# Circuit.net
KiCad netlist of a schematic drawn in EAGLE
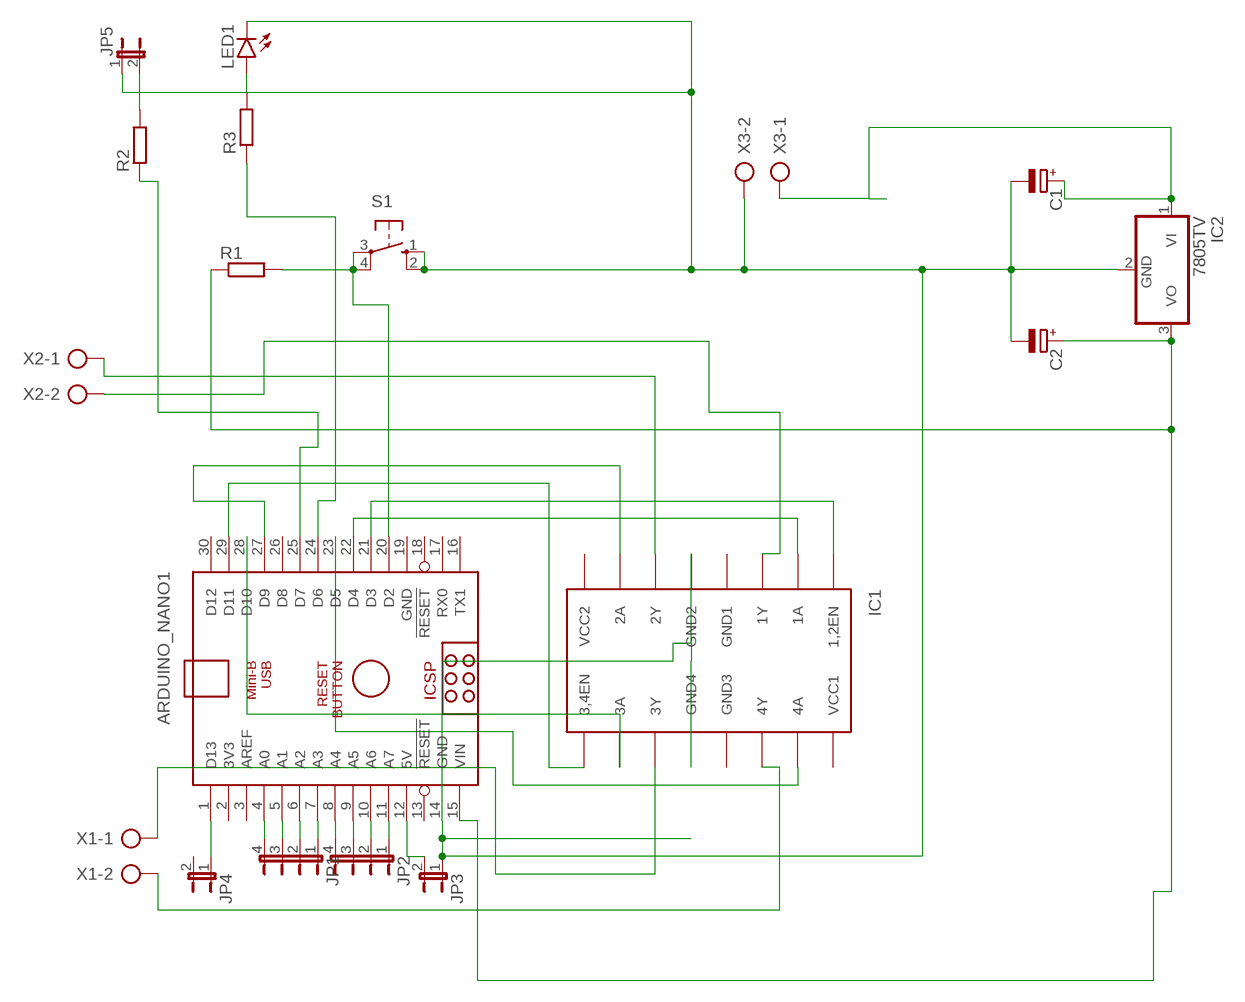
[diagram p0: schematic, sheet 1]

(export (version "E")
  (design (tool "Eeschema 10.0.6"))
  (components
    (comp (ref "ARDUINO_NANO1")
      (value "ARDUINO_NANO")
      (footprint "eagle-import:ARDUINO_NANO")
      (libsource (lib "eagle-import") (part "ARDUINO_NANO"))
    )
    (comp (ref "C1")
      (value "CPOL-EUE2.5-6")
      (footprint "eagle-import:E2,5-6")
      (libsource (lib "eagle-import") (part "CPOL-EUE2.5-6"))
    )
    (comp (ref "C2")
      (value "CPOL-EUE2.5-6")
      (footprint "eagle-import:E2,5-6")
      (libsource (lib "eagle-import") (part "CPOL-EUE2.5-6"))
    )
    (comp (ref "IC1")
      (value "L293D")
      (footprint "eagle-import:DIL16")
      (libsource (lib "eagle-import") (part "L293D"))
    )
    (comp (ref "IC2")
      (value "7805TV")
      (footprint "eagle-import:TO220V")
      (libsource (lib "eagle-import") (part "78TV05"))
    )
    (comp (ref "JP1")
      (value "JP4E")
      (footprint "eagle-import:JP4")
      (libsource (lib "eagle-import") (part "JP4E"))
    )
    (comp (ref "JP2")
      (value "JP4E")
      (footprint "eagle-import:JP4")
      (libsource (lib "eagle-import") (part "JP4E"))
    )
    (comp (ref "JP3")
      (value "JP1E")
      (footprint "eagle-import:JP1")
      (libsource (lib "eagle-import") (part "JP1E"))
    )
    (comp (ref "JP4")
      (value "JP1E")
      (footprint "eagle-import:JP1")
      (libsource (lib "eagle-import") (part "JP1E"))
    )
    (comp (ref "JP5")
      (value "JP1E")
      (footprint "eagle-import:JP1")
      (libsource (lib "eagle-import") (part "JP1E"))
    )
    (comp (ref "LED1")
      (value "LED5MM")
      (footprint "eagle-import:LED5MM")
      (libsource (lib "eagle-import") (part "LED5MM"))
    )
    (comp (ref "R1")
      (value "R-EU_0207/12")
      (footprint "eagle-import:0207_12")
      (libsource (lib "eagle-import") (part "R-EU_0207/12"))
    )
    (comp (ref "R2")
      (value "R-EU_0207/12")
      (footprint "eagle-import:0207_12")
      (libsource (lib "eagle-import") (part "R-EU_0207/12"))
    )
    (comp (ref "R3")
      (value "R-EU_0207/12")
      (footprint "eagle-import:0207_12")
      (libsource (lib "eagle-import") (part "R-EU_0207/12"))
    )
    (comp (ref "S1")
      (value "10-XX")
      (footprint "eagle-import:B3F-10XX")
      (fields (field (name "MPN") "B3F-1000"))
      (libsource (lib "eagle-import") (part "10-XX"))
    )
    (comp (ref "X1")
      (value "AK500/2")
      (footprint "eagle-import:AK500_2")
      (libsource (lib "eagle-import") (part "AK500/2"))
    )
    (comp (ref "X2")
      (value "AK500/2")
      (footprint "eagle-import:AK500_2")
      (libsource (lib "eagle-import") (part "AK500/2"))
    )
    (comp (ref "X3")
      (value "AK500/2")
      (footprint "eagle-import:AK500_2")
      (libsource (lib "eagle-import") (part "AK500/2"))
    )
  )
  (nets
    (net (code "1") (name "/GND") (class "Default")
      (node (ref "ARDUINO_NANO1") (pin "19") (pinfunction "GND_19") (pintype "power_in"))
    )
    (net (code "2") (name "/GND1") (class "Default")
      (node (ref "IC1") (pin "4") (pinfunction "GND1_4") (pintype "power_in"))
    )
    (net (code "3") (name "/GND3") (class "Default")
      (node (ref "IC1") (pin "13") (pinfunction "GND3_13") (pintype "power_in"))
    )
    (net (code "4") (name "/VCC1") (class "Default")
      (node (ref "IC1") (pin "16") (pinfunction "VCC1_16") (pintype "power_in"))
    )
    (net (code "5") (name "/VCC2") (class "Default")
      (node (ref "IC1") (pin "8") (pinfunction "VCC2_8") (pintype "power_in"))
    )
    (net (code "6") (name "Net-(ARDUINO_NANO1-5V)") (class "Default")
      (node (ref "ARDUINO_NANO1") (pin "12") (pinfunction "5V_12") (pintype "power_in"))
      (node (ref "JP3") (pin "2") (pinfunction "2_2") (pintype "passive"))
    )
    (net (code "7") (name "Net-(ARDUINO_NANO1-A0)") (class "Default")
      (node (ref "ARDUINO_NANO1") (pin "4") (pinfunction "A0_4") (pintype "bidirectional"))
      (node (ref "JP1") (pin "4") (pinfunction "4_4") (pintype "passive"))
    )
    (net (code "8") (name "Net-(ARDUINO_NANO1-A1)") (class "Default")
      (node (ref "ARDUINO_NANO1") (pin "5") (pinfunction "A1_5") (pintype "bidirectional"))
      (node (ref "JP1") (pin "3") (pinfunction "3_3") (pintype "passive"))
    )
    (net (code "9") (name "Net-(ARDUINO_NANO1-A2)") (class "Default")
      (node (ref "ARDUINO_NANO1") (pin "6") (pinfunction "A2_6") (pintype "bidirectional"))
      (node (ref "JP1") (pin "2") (pinfunction "2_2") (pintype "passive"))
    )
    (net (code "10") (name "Net-(ARDUINO_NANO1-A3)") (class "Default")
      (node (ref "ARDUINO_NANO1") (pin "7") (pinfunction "A3_7") (pintype "bidirectional"))
      (node (ref "JP1") (pin "1") (pinfunction "1_1") (pintype "passive"))
    )
    (net (code "11") (name "Net-(ARDUINO_NANO1-A4)") (class "Default")
      (node (ref "ARDUINO_NANO1") (pin "8") (pinfunction "A4_8") (pintype "bidirectional"))
      (node (ref "JP2") (pin "4") (pinfunction "4_4") (pintype "passive"))
    )
    (net (code "12") (name "Net-(ARDUINO_NANO1-A5)") (class "Default")
      (node (ref "ARDUINO_NANO1") (pin "9") (pinfunction "A5_9") (pintype "bidirectional"))
      (node (ref "JP2") (pin "3") (pinfunction "3_3") (pintype "passive"))
    )
    (net (code "13") (name "Net-(ARDUINO_NANO1-A6)") (class "Default")
      (node (ref "ARDUINO_NANO1") (pin "10") (pinfunction "A6_10") (pintype "bidirectional"))
      (node (ref "JP2") (pin "2") (pinfunction "2_2") (pintype "passive"))
    )
    (net (code "14") (name "Net-(ARDUINO_NANO1-A7)") (class "Default")
      (node (ref "ARDUINO_NANO1") (pin "11") (pinfunction "A7_11") (pintype "bidirectional"))
      (node (ref "JP2") (pin "1") (pinfunction "1_1") (pintype "passive"))
    )
    (net (code "15") (name "Net-(ARDUINO_NANO1-D2)") (class "Default")
      (node (ref "ARDUINO_NANO1") (pin "20") (pinfunction "D2_20") (pintype "bidirectional"))
      (node (ref "R1") (pin "2") (pinfunction "2_2") (pintype "passive"))
      (node (ref "S1") (pin "3") (pinfunction "P_3") (pintype "passive"))
      (node (ref "S1") (pin "4") (pinfunction "P1_4") (pintype "passive"))
    )
    (net (code "16") (name "Net-(ARDUINO_NANO1-D3)") (class "Default")
      (node (ref "ARDUINO_NANO1") (pin "21") (pinfunction "D3_21") (pintype "bidirectional"))
      (node (ref "IC1") (pin "1") (pinfunction "1,2EN_1") (pintype "input"))
    )
    (net (code "17") (name "Net-(ARDUINO_NANO1-D4)") (class "Default")
      (node (ref "ARDUINO_NANO1") (pin "22") (pinfunction "D4_22") (pintype "bidirectional"))
      (node (ref "IC1") (pin "2") (pinfunction "1A_2") (pintype "input"))
    )
    (net (code "18") (name "Net-(ARDUINO_NANO1-D5)") (class "Default")
      (node (ref "ARDUINO_NANO1") (pin "23") (pinfunction "D5_23") (pintype "bidirectional"))
      (node (ref "IC1") (pin "15") (pinfunction "4A_15") (pintype "input"))
    )
    (net (code "19") (name "Net-(ARDUINO_NANO1-D6)") (class "Default")
      (node (ref "ARDUINO_NANO1") (pin "24") (pinfunction "D6_24") (pintype "bidirectional"))
      (node (ref "R3") (pin "1") (pinfunction "1_1") (pintype "passive"))
    )
    (net (code "20") (name "Net-(ARDUINO_NANO1-D7)") (class "Default")
      (node (ref "ARDUINO_NANO1") (pin "25") (pinfunction "D7_25") (pintype "bidirectional"))
      (node (ref "R2") (pin "1") (pinfunction "1_1") (pintype "passive"))
    )
    (net (code "21") (name "Net-(ARDUINO_NANO1-D9)") (class "Default")
      (node (ref "ARDUINO_NANO1") (pin "27") (pinfunction "D9_27") (pintype "bidirectional"))
      (node (ref "IC1") (pin "7") (pinfunction "2A_7") (pintype "input"))
    )
    (net (code "22") (name "Net-(ARDUINO_NANO1-D10)") (class "Default")
      (node (ref "ARDUINO_NANO1") (pin "28") (pinfunction "D10_28") (pintype "bidirectional"))
      (node (ref "IC1") (pin "10") (pinfunction "3A_10") (pintype "input"))
    )
    (net (code "23") (name "Net-(ARDUINO_NANO1-D11)") (class "Default")
      (node (ref "ARDUINO_NANO1") (pin "29") (pinfunction "D11_29") (pintype "bidirectional"))
      (node (ref "IC1") (pin "9") (pinfunction "3,4EN_9") (pintype "input"))
    )
    (net (code "24") (name "Net-(ARDUINO_NANO1-D13)") (class "Default")
      (node (ref "ARDUINO_NANO1") (pin "1") (pinfunction "D13_1") (pintype "bidirectional"))
      (node (ref "JP4") (pin "1") (pinfunction "1_1") (pintype "passive"))
    )
    (net (code "25") (name "Net-(ARDUINO_NANO1-VIN)") (class "Default")
      (node (ref "ARDUINO_NANO1") (pin "15") (pinfunction "VIN_15") (pintype "power_in"))
      (node (ref "C2") (pin "+") (pinfunction "+_+") (pintype "passive"))
      (node (ref "IC2") (pin "3") (pinfunction "VO_3") (pintype "passive"))
      (node (ref "R1") (pin "1") (pinfunction "1_1") (pintype "passive"))
    )
    (net (code "26") (name "Net-(IC1-1Y)") (class "Default")
      (node (ref "IC1") (pin "3") (pinfunction "1Y_3") (pintype "output"))
      (node (ref "X2") (pin "2") (pinfunction "KL_2") (pintype "passive"))
    )
    (net (code "27") (name "Net-(IC1-2Y)") (class "Default")
      (node (ref "IC1") (pin "6") (pinfunction "2Y_6") (pintype "output"))
      (node (ref "X2") (pin "1") (pinfunction "KL_1") (pintype "passive"))
    )
    (net (code "28") (name "Net-(IC1-3Y)") (class "Default")
      (node (ref "IC1") (pin "11") (pinfunction "3Y_11") (pintype "output"))
      (node (ref "X1") (pin "1") (pinfunction "KL_1") (pintype "passive"))
    )
    (net (code "29") (name "Net-(IC1-4Y)") (class "Default")
      (node (ref "IC1") (pin "14") (pinfunction "4Y_14") (pintype "output"))
      (node (ref "X1") (pin "2") (pinfunction "KL_2") (pintype "passive"))
    )
    (net (code "30") (name "Net-(IC1-GND2)") (class "Default")
      (node (ref "ARDUINO_NANO1") (pin "14") (pinfunction "GND_14") (pintype "power_in"))
      (node (ref "C1") (pin "-") (pinfunction "-_-") (pintype "passive"))
      (node (ref "C2") (pin "-") (pinfunction "-_-") (pintype "passive"))
      (node (ref "IC1") (pin "12") (pinfunction "GND4_12") (pintype "power_in"))
      (node (ref "IC1") (pin "5") (pinfunction "GND2_5") (pintype "power_in"))
      (node (ref "IC2") (pin "2") (pinfunction "GND_2") (pintype "passive"))
      (node (ref "JP3") (pin "1") (pinfunction "1_1") (pintype "passive"))
      (node (ref "JP5") (pin "1") (pinfunction "1_1") (pintype "passive"))
      (node (ref "LED1") (pin "K") (pinfunction "C_K") (pintype "passive"))
      (node (ref "S1") (pin "1") (pinfunction "S_1") (pintype "passive"))
      (node (ref "S1") (pin "2") (pinfunction "S1_2") (pintype "passive"))
      (node (ref "X3") (pin "2") (pinfunction "KL_2") (pintype "passive"))
    )
    (net (code "31") (name "Net-(IC2-VI)") (class "Default")
      (node (ref "C1") (pin "+") (pinfunction "+_+") (pintype "passive"))
      (node (ref "IC2") (pin "1") (pinfunction "VI_1") (pintype "input"))
      (node (ref "X3") (pin "1") (pinfunction "KL_1") (pintype "passive"))
    )
    (net (code "32") (name "Net-(JP5-Pad2)") (class "Default")
      (node (ref "JP5") (pin "2") (pinfunction "2_2") (pintype "passive"))
      (node (ref "R2") (pin "2") (pinfunction "2_2") (pintype "passive"))
    )
    (net (code "33") (name "Net-(LED1-PadA)") (class "Default")
      (node (ref "LED1") (pin "A") (pinfunction "A_A") (pintype "passive"))
      (node (ref "R3") (pin "2") (pinfunction "2_2") (pintype "passive"))
    )
    (net (code "34") (name "unconnected-(ARDUINO_NANO1-3V3-Pad2)") (class "Default")
      (node (ref "ARDUINO_NANO1") (pin "2") (pinfunction "3V3_2") (pintype "output"))
    )
    (net (code "35") (name "unconnected-(ARDUINO_NANO1-AREF-Pad3)") (class "Default")
      (node (ref "ARDUINO_NANO1") (pin "3") (pinfunction "AREF_3") (pintype "input"))
    )
    (net (code "36") (name "unconnected-(ARDUINO_NANO1-D8-Pad26)") (class "Default")
      (node (ref "ARDUINO_NANO1") (pin "26") (pinfunction "D8_26") (pintype "bidirectional"))
    )
    (net (code "37") (name "unconnected-(ARDUINO_NANO1-D12-Pad30)") (class "Default")
      (node (ref "ARDUINO_NANO1") (pin "30") (pinfunction "D12_30") (pintype "bidirectional"))
    )
    (net (code "38") (name "unconnected-(ARDUINO_NANO1-RX0-Pad17)") (class "Default")
      (node (ref "ARDUINO_NANO1") (pin "17") (pinfunction "RX0_17") (pintype "bidirectional"))
    )
    (net (code "39") (name "unconnected-(ARDUINO_NANO1-TX1-Pad16)") (class "Default")
      (node (ref "ARDUINO_NANO1") (pin "16") (pinfunction "TX1_16") (pintype "bidirectional"))
    )
    (net (code "40") (name "unconnected-(ARDUINO_NANO1-~{RESET}-Pad13)") (class "Default")
      (node (ref "ARDUINO_NANO1") (pin "13") (pinfunction "~{RESET}_13") (pintype "input"))
    )
    (net (code "41") (name "unconnected-(ARDUINO_NANO1-~{RESET}-Pad18)") (class "Default")
      (node (ref "ARDUINO_NANO1") (pin "18") (pinfunction "~{RESET}_18") (pintype "input"))
    )
    (net (code "42") (name "unconnected-(JP4-Pad2)") (class "Default")
      (node (ref "JP4") (pin "2") (pinfunction "2_2") (pintype "passive"))
    )
  )
)
